# MotorController_ControlV1_1.net
KiCad netlist of a schematic drawn in Altium Designer
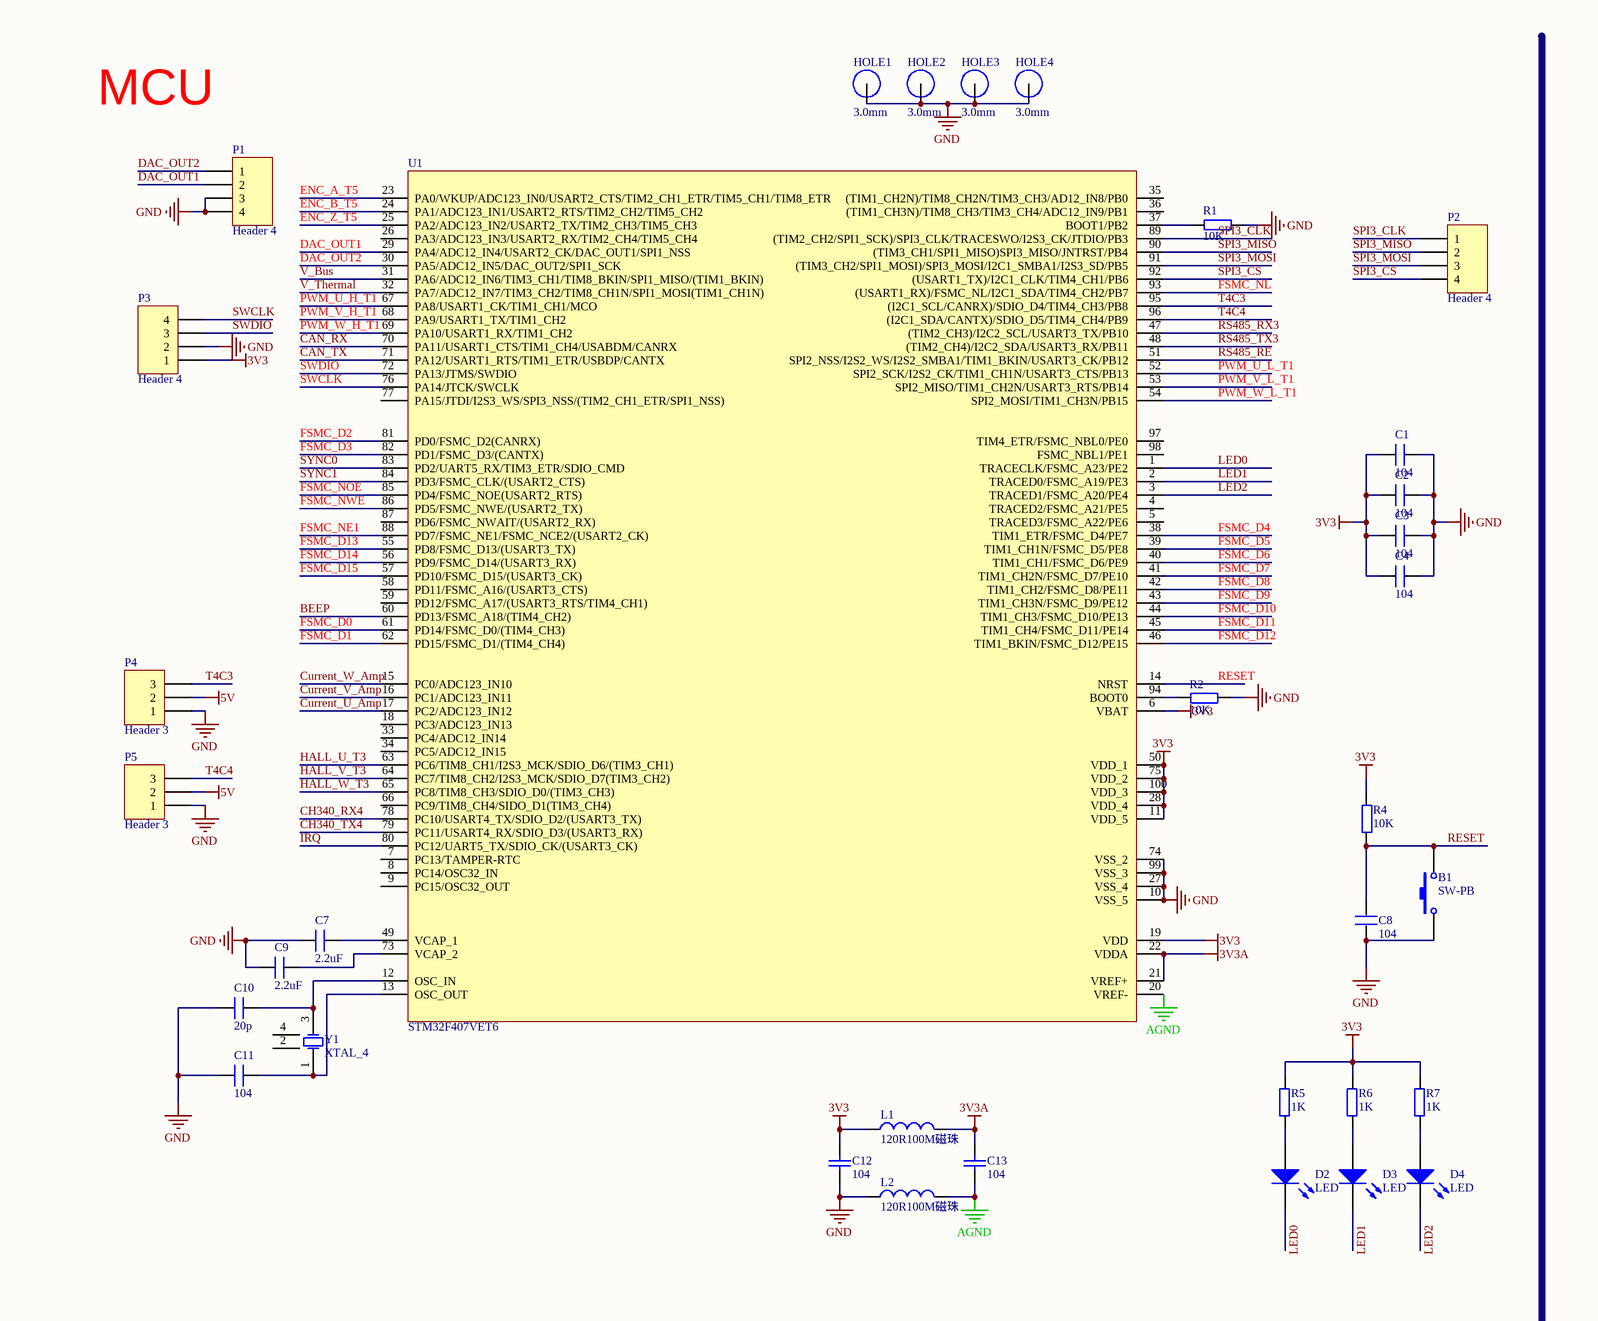
[diagram p0: MotorController_ControlV1.1.SchDoc, top left]
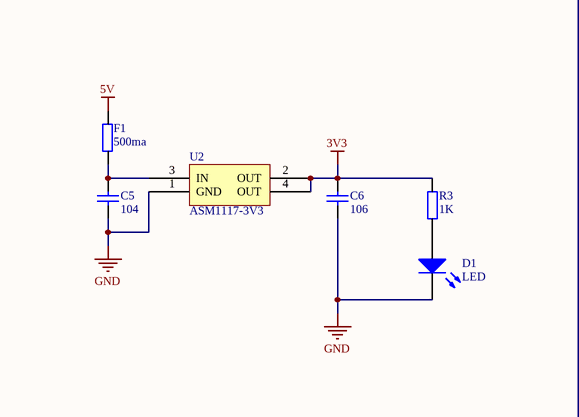
[diagram p1: MotorController_ControlV1.1.SchDoc, top middle]
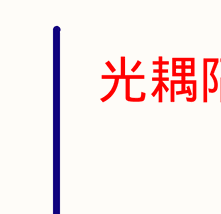
[diagram p2: MotorController_ControlV1.1.SchDoc, top right]
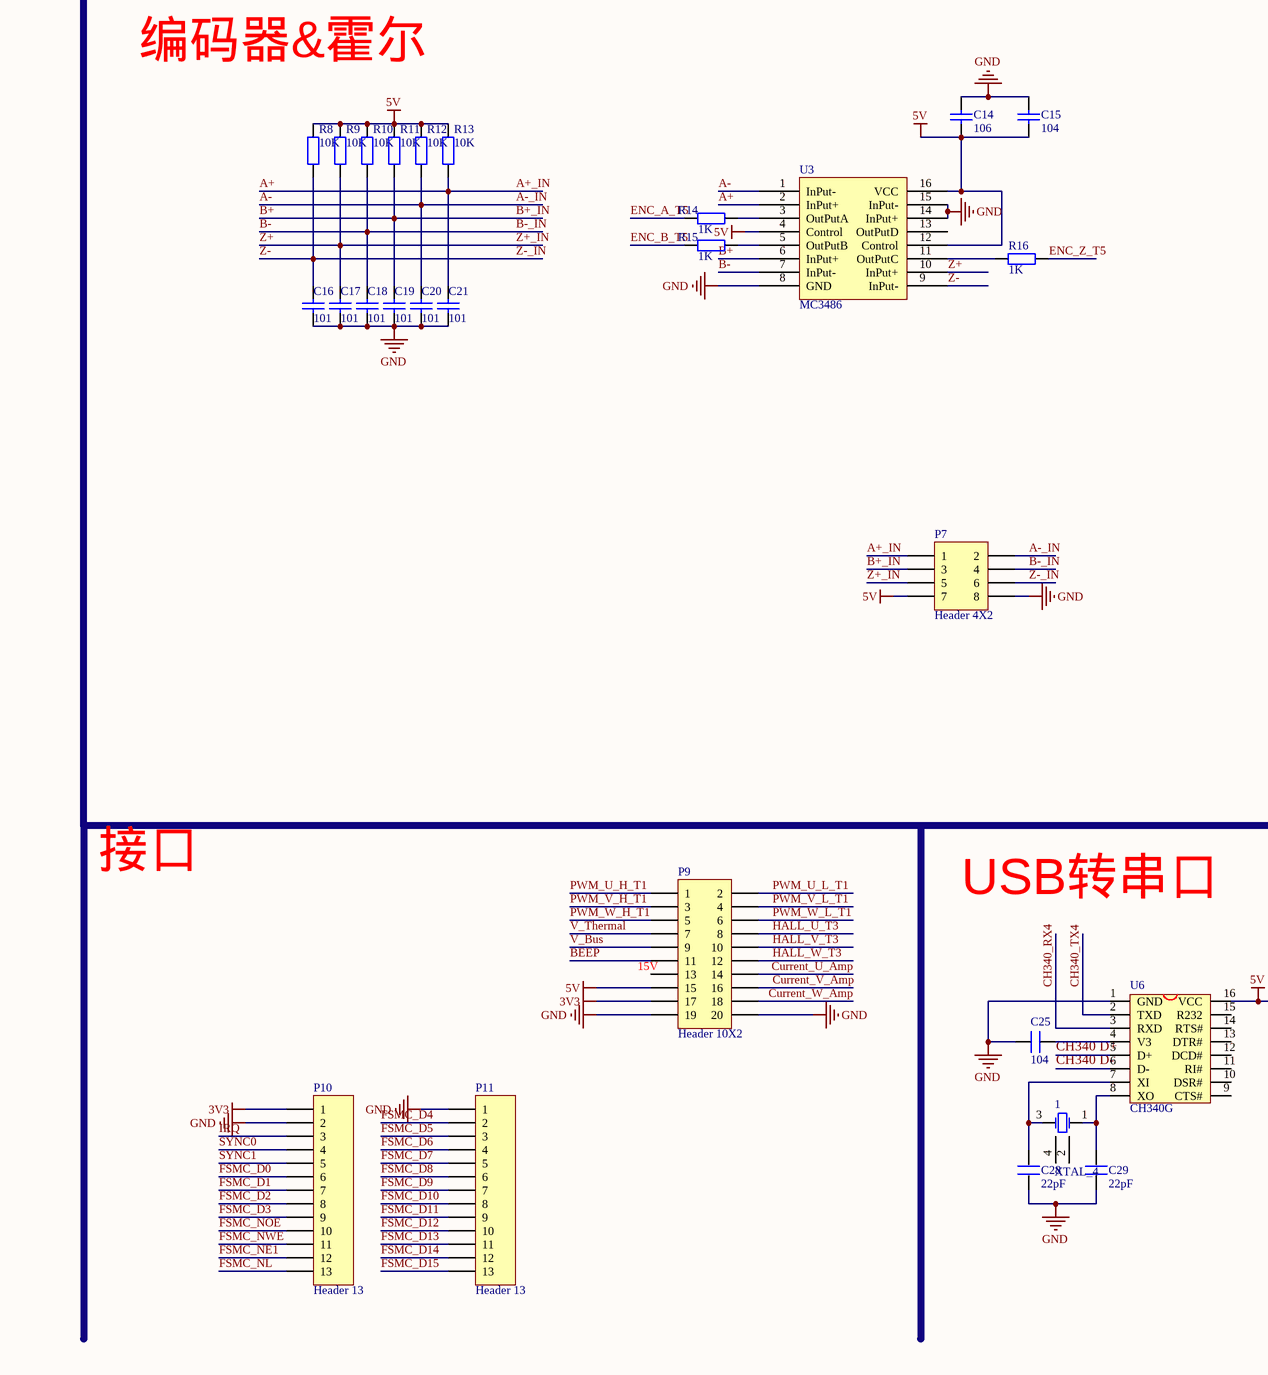
[diagram p3: MotorController_ControlV1.1.SchDoc, bottom middle]
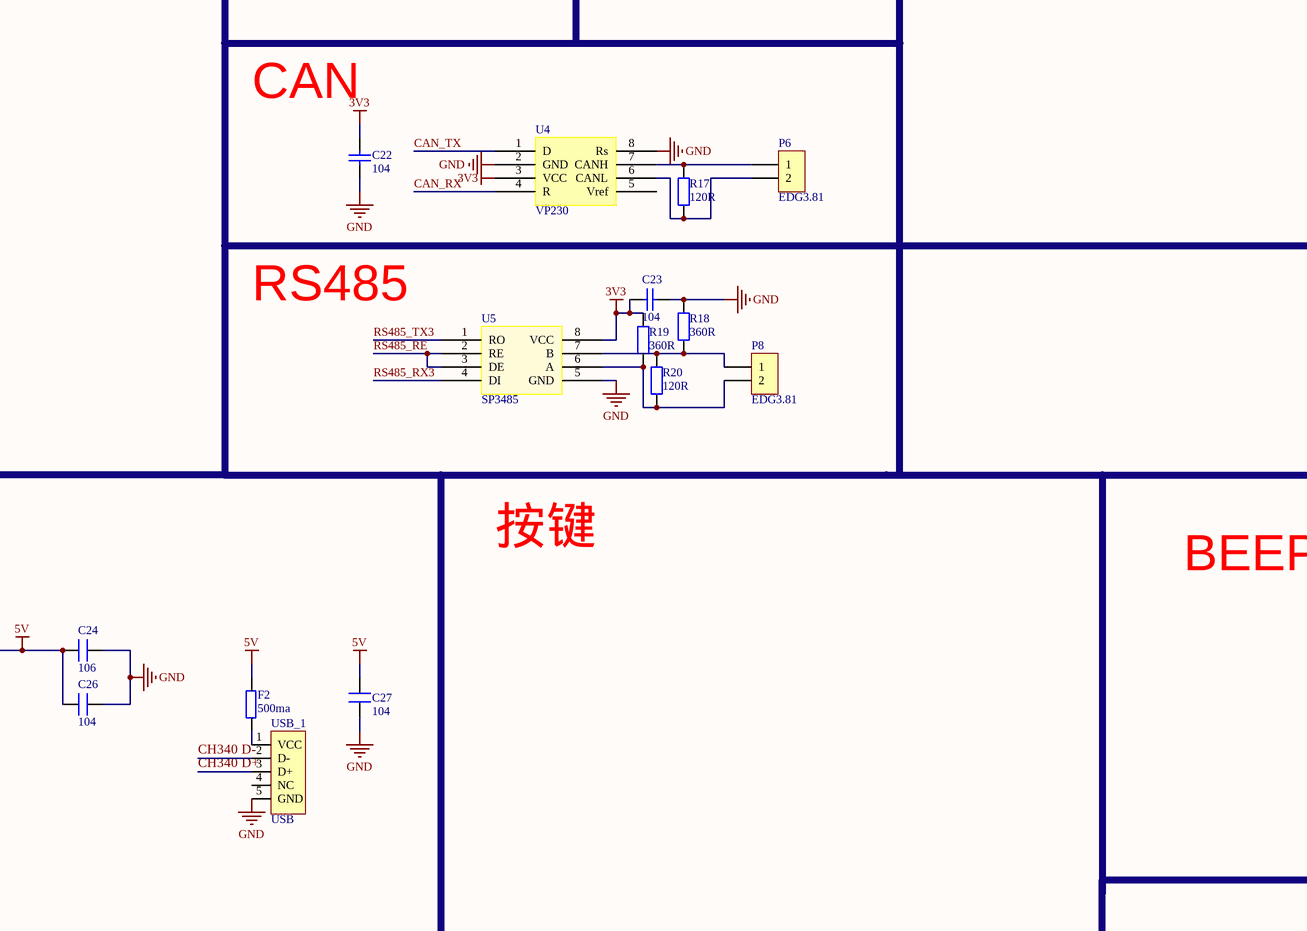
[diagram p4: MotorController_ControlV1.1.SchDoc, bottom right]

(export (version "E")
  (design (tool "Eeschema 10.0.6"))
  (components
    (comp (ref "1")
      (value "XTAL_4")
      (footprint "OSC 3225-4P")
      (description "Crystal Oscillator")
      (fields (field (name "PUBLISHER") "Altium Limited"))
      (libsource (lib "MYSchlib") (part "XTAL_4"))
    )
    (comp (ref "B1")
      (value "SW-PB")
      (footprint "TSW DIP-3*6*5_V")
      (description "Switch")
      (fields (field (name "PUBLISHER") "Altium Limited"))
      (libsource (lib "Miscellaneous Devices") (part "SW-PB"))
    )
    (comp (ref "C1") (value "104") (footprint "0603_C") (libsource (lib "MYSchlib") (part "C")))
    (comp (ref "C2") (value "104") (footprint "0603_C") (libsource (lib "MYSchlib") (part "C")))
    (comp (ref "C3") (value "104") (footprint "0603_C") (libsource (lib "MYSchlib") (part "C")))
    (comp (ref "C4") (value "104") (footprint "0603_C") (libsource (lib "MYSchlib") (part "C")))
    (comp (ref "C5")
      (value "104")
      (footprint "0603_C")
      (description "C")
      (fields (field (name "PUBLISHER") "Altium Limited"))
      (libsource (lib "RLC") (part "C"))
    )
    (comp (ref "C6")
      (value "106")
      (footprint "0603_C")
      (description "C")
      (fields (field (name "PUBLISHER") "Altium Limited"))
      (libsource (lib "RLC") (part "C"))
    )
    (comp (ref "C7") (value "2.2uF") (footprint "0603_C") (libsource (lib "MYSchlib") (part "C")))
    (comp (ref "C8") (value "104") (footprint "0603_C") (libsource (lib "MYSchlib") (part "C")))
    (comp (ref "C9") (value "2.2uF") (footprint "0603_C") (libsource (lib "MYSchlib") (part "C")))
    (comp (ref "C10") (value "20p") (footprint "0603_C") (libsource (lib "MYSchlib") (part "C")))
    (comp (ref "C11") (value "104") (footprint "0603_C") (libsource (lib "MYSchlib") (part "C")))
    (comp (ref "C12")
      (value "104")
      (footprint "0603_C")
      (description "C")
      (fields (field (name "PUBLISHER") "Altium Limited"))
      (libsource (lib "RLC") (part "C"))
    )
    (comp (ref "C13")
      (value "104")
      (footprint "0603_C")
      (description "C")
      (fields (field (name "PUBLISHER") "Altium Limited"))
      (libsource (lib "RLC") (part "C"))
    )
    (comp (ref "C14")
      (value "106")
      (footprint "0603_C")
      (description "Capacitor")
      (fields (field (name "Comment") "Cap") (field (name "PUBLISHER") "Altium Limited"))
      (libsource (lib "Miscellaneous Devices") (part "Cap"))
    )
    (comp (ref "C15")
      (value "104")
      (footprint "0603_C")
      (description "Capacitor")
      (fields (field (name "Comment") "Cap") (field (name "PUBLISHER") "Altium Limited"))
      (libsource (lib "Miscellaneous Devices") (part "Cap"))
    )
    (comp (ref "C16")
      (value "101")
      (footprint "0603_C")
      (description "Capacitor")
      (fields (field (name "Comment") "Cap") (field (name "PUBLISHER") "Altium Limited"))
      (libsource (lib "Miscellaneous Devices") (part "Cap"))
    )
    (comp (ref "C17")
      (value "101")
      (footprint "0603_C")
      (description "Capacitor")
      (fields (field (name "Comment") "Cap") (field (name "PUBLISHER") "Altium Limited"))
      (libsource (lib "Miscellaneous Devices") (part "Cap"))
    )
    (comp (ref "C18")
      (value "101")
      (footprint "0603_C")
      (description "Capacitor")
      (fields (field (name "Comment") "Cap") (field (name "PUBLISHER") "Altium Limited"))
      (libsource (lib "Miscellaneous Devices") (part "Cap"))
    )
    (comp (ref "C19")
      (value "101")
      (footprint "0603_C")
      (description "Capacitor")
      (fields (field (name "Comment") "Cap") (field (name "PUBLISHER") "Altium Limited"))
      (libsource (lib "Miscellaneous Devices") (part "Cap"))
    )
    (comp (ref "C20")
      (value "101")
      (footprint "0603_C")
      (description "Capacitor")
      (fields (field (name "Comment") "Cap") (field (name "PUBLISHER") "Altium Limited"))
      (libsource (lib "Miscellaneous Devices") (part "Cap"))
    )
    (comp (ref "C21")
      (value "101")
      (footprint "0603_C")
      (description "Capacitor")
      (fields (field (name "Comment") "Cap") (field (name "PUBLISHER") "Altium Limited"))
      (libsource (lib "Miscellaneous Devices") (part "Cap"))
    )
    (comp (ref "C22")
      (value "104")
      (footprint "0603_C")
      (description "Capacitor")
      (fields (field (name "Comment") "Cap") (field (name "PUBLISHER") "Altium Limited"))
      (libsource (lib "Miscellaneous Devices") (part "Cap"))
    )
    (comp (ref "C23")
      (value "104")
      (footprint "0603_C")
      (description "Capacitor")
      (fields (field (name "Comment") "Cap") (field (name "PUBLISHER") "Altium Limited"))
      (libsource (lib "Miscellaneous Devices") (part "Cap"))
    )
    (comp (ref "C24") (value "106") (footprint "0603_C") (libsource (lib "战舰STM32开发板底板封装库") (part "C")))
    (comp (ref "C25") (value "104") (footprint "0603_C") (libsource (lib "战舰STM32开发板底板封装库") (part "C")))
    (comp (ref "C26") (value "104") (footprint "0603_C") (libsource (lib "战舰STM32开发板底板封装库") (part "C")))
    (comp (ref "C27") (value "104") (footprint "0603_C") (libsource (lib "战舰STM32开发板底板封装库") (part "C")))
    (comp (ref "C28") (value "22pF") (footprint "0603_C") (libsource (lib "战舰STM32开发板底板封装库") (part "C")))
    (comp (ref "C29") (value "22pF") (footprint "0603_C") (libsource (lib "战舰STM32开发板底板封装库") (part "C")))
    (comp (ref "D1") (value "LED") (footprint "0603_LED") (libsource (lib "MYSchlib") (part "LED")))
    (comp (ref "D2") (value "LED") (footprint "0603_LED") (libsource (lib "MYSchlib") (part "LED")))
    (comp (ref "D3") (value "LED") (footprint "0603_LED") (libsource (lib "MYSchlib") (part "LED")))
    (comp (ref "D4") (value "LED") (footprint "0603_LED") (libsource (lib "MYSchlib") (part "LED")))
    (comp (ref "F1") (value "500ma") (footprint "FU 0805") (libsource (lib "MYSchlib") (part "R")))
    (comp (ref "F2") (value "500ma") (footprint "FU 0805") (libsource (lib "MYSchlib") (part "R")))
    (comp (ref "HOLE1")
      (value "3.0mm")
      (footprint "M2.5x6+6_L")
      (fields (field (name "Comment") "HOLE"))
      (libsource (lib "MYSchlib") (part "HOLE"))
    )
    (comp (ref "HOLE2")
      (value "3.0mm")
      (footprint "M2.5x6+6_L")
      (fields (field (name "Comment") "HOLE"))
      (libsource (lib "MYSchlib") (part "HOLE"))
    )
    (comp (ref "HOLE3")
      (value "3.0mm")
      (footprint "M2.5x6+6_L")
      (fields (field (name "Comment") "HOLE"))
      (libsource (lib "MYSchlib") (part "HOLE"))
    )
    (comp (ref "HOLE4")
      (value "3.0mm")
      (footprint "M2.5x6+6_L")
      (fields (field (name "Comment") "HOLE"))
      (libsource (lib "MYSchlib") (part "HOLE"))
    )
    (comp (ref "L1")
      (value "120R100M磁珠")
      (footprint "0603_R")
      (description "L")
      (fields (field (name "PUBLISHER") "Altium Limited"))
      (libsource (lib "MYSchlib") (part "L_1"))
    )
    (comp (ref "L2")
      (value "120R100M磁珠")
      (footprint "0603_R")
      (description "L")
      (fields (field (name "PUBLISHER") "Altium Limited"))
      (libsource (lib "MYSchlib") (part "L_1"))
    )
    (comp (ref "P1")
      (value "Header 4")
      (footprint "HDR2.54-LI-4P")
      (description "Header, 4-Pin")
      (fields (field (name "PUBLISHER") "Altium Limited"))
      (libsource (lib "Miscellaneous Connectors") (part "Header 4"))
    )
    (comp (ref "P2")
      (value "Header 4")
      (footprint "HDR1X4")
      (description "Header, 4-Pin")
      (fields (field (name "PUBLISHER") "Altium Limited"))
      (libsource (lib "Miscellaneous Connectors") (part "Header 4"))
    )
    (comp (ref "P3")
      (value "Header 4")
      (footprint "HDR1X4")
      (description "Header, 4-Pin")
      (fields (field (name "PUBLISHER") "Altium Limited"))
      (libsource (lib "MYSchlib") (part "Header 4"))
    )
    (comp (ref "P4")
      (value "Header 3")
      (footprint "HDR1X3")
      (description "Header, 3-Pin")
      (fields (field (name "PUBLISHER") "Altium Limited"))
      (libsource (lib "Miscellaneous Connectors") (part "Header 3"))
    )
    (comp (ref "P5")
      (value "Header 3")
      (footprint "HDR1X3")
      (description "Header, 3-Pin")
      (fields (field (name "PUBLISHER") "Altium Limited"))
      (libsource (lib "Miscellaneous Connectors") (part "Header 3"))
    )
    (comp (ref "P6")
      (value "EDG3.81")
      (footprint "3.81EDG_2*1W")
      (fields (field (name "PUBLISHER") "Altium Limited"))
      (libsource (lib "MYSchlib") (part "HT3.96"))
    )
    (comp (ref "P7")
      (value "Header 4X2")
      (footprint "MYPcbLib:HDR2.54-WI-2x4P")
      (description "Header, 4-Pin, Dual row")
      (fields (field (name "PUBLISHER") "Altium Limited"))
      (libsource (lib "Miscellaneous Connectors") (part "Header 4X2"))
    )
    (comp (ref "P8")
      (value "EDG3.81")
      (footprint "3.81EDG_2*1W")
      (fields (field (name "PUBLISHER") "Altium Limited"))
      (libsource (lib "MYSchlib") (part "HT3.96"))
    )
    (comp (ref "P9")
      (value "Header 10X2")
      (footprint "MYPcbLib:HDR2.54-LI-2x10P")
      (description "Header, 10-Pin, Dual row")
      (fields (field (name "PUBLISHER") "Altium Limited"))
      (libsource (lib "Miscellaneous Connectors") (part "Header 10X2"))
    )
    (comp (ref "P10")
      (value "Header 13")
      (footprint "HDR2.54-LI-13P")
      (description "Header, 13-Pin")
      (fields (field (name "PUBLISHER") "Altium Limited"))
      (libsource (lib "Miscellaneous Connectors") (part "Header 13"))
    )
    (comp (ref "P11")
      (value "Header 13")
      (footprint "HDR2.54-LI-13P")
      (description "Header, 13-Pin")
      (fields (field (name "PUBLISHER") "Altium Limited"))
      (libsource (lib "Miscellaneous Connectors") (part "Header 13"))
    )
    (comp (ref "R1") (value "10K") (footprint "0603_R") (libsource (lib "MYSchlib") (part "R")))
    (comp (ref "R2") (value "10K") (footprint "0603_R") (libsource (lib "MYSchlib") (part "R")))
    (comp (ref "R3") (value "1K") (footprint "0603_R") (libsource (lib "MYSchlib") (part "R")))
    (comp (ref "R4") (value "10K") (footprint "0603_R") (libsource (lib "MYSchlib") (part "R")))
    (comp (ref "R5") (value "1K") (footprint "0603_R") (libsource (lib "MYSchlib") (part "R")))
    (comp (ref "R6") (value "1K") (footprint "0603_R") (libsource (lib "MYSchlib") (part "R")))
    (comp (ref "R7") (value "1K") (footprint "0603_R") (libsource (lib "MYSchlib") (part "R")))
    (comp (ref "R8")
      (value "10K")
      (footprint "0603_R")
      (description "Resistor")
      (fields (field (name "Comment") "Res2") (field (name "PUBLISHER") "Altium Limited"))
      (libsource (lib "Miscellaneous Devices") (part "Res2"))
    )
    (comp (ref "R9")
      (value "10K")
      (footprint "0603_R")
      (description "Resistor")
      (fields (field (name "Comment") "Res2") (field (name "PUBLISHER") "Altium Limited"))
      (libsource (lib "Miscellaneous Devices") (part "Res2"))
    )
    (comp (ref "R10")
      (value "10K")
      (footprint "0603_R")
      (description "Resistor")
      (fields (field (name "Comment") "Res2") (field (name "PUBLISHER") "Altium Limited"))
      (libsource (lib "Miscellaneous Devices") (part "Res2"))
    )
    (comp (ref "R11")
      (value "10K")
      (footprint "0603_R")
      (description "Resistor")
      (fields (field (name "Comment") "Res2") (field (name "PUBLISHER") "Altium Limited"))
      (libsource (lib "Miscellaneous Devices") (part "Res2"))
    )
    (comp (ref "R12")
      (value "10K")
      (footprint "0603_R")
      (description "Resistor")
      (fields (field (name "Comment") "Res2") (field (name "PUBLISHER") "Altium Limited"))
      (libsource (lib "Miscellaneous Devices") (part "Res2"))
    )
    (comp (ref "R13")
      (value "10K")
      (footprint "0603_R")
      (description "Resistor")
      (fields (field (name "Comment") "Res2") (field (name "PUBLISHER") "Altium Limited"))
      (libsource (lib "Miscellaneous Devices") (part "Res2"))
    )
    (comp (ref "R14")
      (value "1K")
      (footprint "0603_R")
      (description "Resistor")
      (fields (field (name "Comment") "Res2") (field (name "PUBLISHER") "Altium Limited"))
      (libsource (lib "") (part "Res2_1"))
    )
    (comp (ref "R15")
      (value "1K")
      (footprint "0603_R")
      (description "Resistor")
      (fields (field (name "Comment") "Res2") (field (name "PUBLISHER") "Altium Limited"))
      (libsource (lib "") (part "Res2_1"))
    )
    (comp (ref "R16")
      (value "1K")
      (footprint "0603_R")
      (description "Resistor")
      (fields (field (name "Comment") "Res2") (field (name "PUBLISHER") "Altium Limited"))
      (libsource (lib "") (part "Res2_2"))
    )
    (comp (ref "R17")
      (value "120R")
      (footprint "0603_R")
      (description "Resistor")
      (fields (field (name "Comment") "Res2") (field (name "PUBLISHER") "Altium Limited"))
      (libsource (lib "MySchLib") (part "Res2"))
    )
    (comp (ref "R18")
      (value "360R")
      (footprint "0603_R")
      (description "Resistor")
      (fields (field (name "Comment") "Res2") (field (name "PUBLISHER") "Altium Limited"))
      (libsource (lib "MySchLib") (part "Res2"))
    )
    (comp (ref "R19")
      (value "360R")
      (footprint "0603_R")
      (description "Resistor")
      (fields (field (name "Comment") "Res2") (field (name "PUBLISHER") "Altium Limited"))
      (libsource (lib "MySchLib") (part "Res2"))
    )
    (comp (ref "R20")
      (value "120R")
      (footprint "0603_R")
      (description "Resistor")
      (fields (field (name "Comment") "Res2") (field (name "PUBLISHER") "Altium Limited"))
      (libsource (lib "MySchLib") (part "Res2"))
    )
    (comp (ref "U1")
      (value "STM32F407VET6")
      (footprint "LQFP-100_M")
      (libsource (lib "MYSchlib") (part "STM32F407VET6"))
    )
    (comp (ref "U2")
      (value "ASM1117-3V3")
      (footprint "SOT-223")
      (description "3.3V稳压芯片")
      (libsource (lib "MYSchlib") (part "ASM1117"))
    )
    (comp (ref "U3") (value "MC3486") (footprint "SO-16N") (libsource (lib "AM26LS32") (part "Component_1")))
    (comp (ref "U4") (value "VP230") (footprint "SOP-8") (libsource (lib "MYSchlib") (part "VP230")))
    (comp (ref "U5") (value "SP3485") (footprint "SOP-8") (libsource (lib "MYSchlib") (part "SP3485")))
    (comp (ref "U6")
      (value "CH340G")
      (footprint "SOP16")
      (description "USB2UART")
      (libsource (lib "MYSchlib") (part "CH340G"))
    )
    (comp (ref "USB_1") (value "USB") (footprint "USB_AB") (libsource (lib "战舰STM32开发板底板封装库") (part "USB5")))
    (comp (ref "Y1")
      (value "XTAL_4")
      (footprint "OSC 5032-4P")
      (description "Crystal Oscillator")
      (fields (field (name "PUBLISHER") "Altium Limited"))
      (libsource (lib "MYSchlib") (part "XTAL_4"))
    )
  )
  (nets
    (net (code "1") (name "/A+") (class "Default")
      (node (ref "C21") (pin "1") (pinfunction "1_1") (pintype "passive"))
      (node (ref "P7") (pin "1") (pinfunction "1_1") (pintype "passive"))
      (node (ref "R13") (pin "2") (pinfunction "2_2") (pintype "passive"))
      (node (ref "U3") (pin "2") (pinfunction "InPut+_2") (pintype "passive"))
    )
    (net (code "2") (name "/A-") (class "Default")
      (node (ref "C20") (pin "1") (pinfunction "1_1") (pintype "passive"))
      (node (ref "P7") (pin "2") (pinfunction "2_2") (pintype "passive"))
      (node (ref "R12") (pin "2") (pinfunction "2_2") (pintype "passive"))
      (node (ref "U3") (pin "1") (pinfunction "InPut-_1") (pintype "passive"))
    )
    (net (code "3") (name "/B+") (class "Default")
      (node (ref "C19") (pin "1") (pinfunction "1_1") (pintype "passive"))
      (node (ref "P7") (pin "3") (pinfunction "3_3") (pintype "passive"))
      (node (ref "R11") (pin "2") (pinfunction "2_2") (pintype "passive"))
      (node (ref "U3") (pin "6") (pinfunction "InPut+_6") (pintype "passive"))
    )
    (net (code "4") (name "/B-") (class "Default")
      (node (ref "C18") (pin "1") (pinfunction "1_1") (pintype "passive"))
      (node (ref "P7") (pin "4") (pinfunction "4_4") (pintype "passive"))
      (node (ref "R10") (pin "2") (pinfunction "2_2") (pintype "passive"))
      (node (ref "U3") (pin "7") (pinfunction "InPut-_7") (pintype "passive"))
    )
    (net (code "5") (name "/BEEP") (class "Default")
      (node (ref "P9") (pin "11") (pinfunction "11_11") (pintype "passive"))
      (node (ref "U1") (pin "60") (pinfunction "PD13/FSMC_A18/(TIM4_CH2)_60") (pintype "passive"))
    )
    (net (code "6") (name "/CAN_RX") (class "Default")
      (node (ref "U1") (pin "70") (pinfunction "PA11/USART1_CTS/TIM1_CH4/USABDM/CANRX_70") (pintype "passive"))
      (node (ref "U4") (pin "4") (pinfunction "R_4") (pintype "passive"))
    )
    (net (code "7") (name "/CAN_TX") (class "Default")
      (node (ref "U1") (pin "71") (pinfunction "PA12/USART1_RTS/TIM1_ETR/USBDP/CANTX_71") (pintype "passive"))
      (node (ref "U4") (pin "1") (pinfunction "D_1") (pintype "passive"))
    )
    (net (code "8") (name "/CH340 D+") (class "Default")
      (node (ref "U6") (pin "5") (pinfunction "D+_5") (pintype "passive"))
      (node (ref "USB_1") (pin "3") (pinfunction "D+_3") (pintype "passive"))
    )
    (net (code "9") (name "/CH340 D-") (class "Default")
      (node (ref "U6") (pin "6") (pinfunction "D-_6") (pintype "passive"))
      (node (ref "USB_1") (pin "2") (pinfunction "D-_2") (pintype "passive"))
    )
    (net (code "10") (name "/CH340_RX4") (class "Default")
      (node (ref "U1") (pin "78") (pinfunction "PC10/USART4_TX/SDIO_D2/(USART3_TX)_78") (pintype "passive"))
      (node (ref "U6") (pin "3") (pinfunction "RXD_3") (pintype "passive"))
    )
    (net (code "11") (name "/CH340_TX4") (class "Default")
      (node (ref "U1") (pin "79") (pinfunction "PC11/USART4_RX/SDIO_D3/(USART3_RX)_79") (pintype "passive"))
      (node (ref "U6") (pin "2") (pinfunction "TXD_2") (pintype "passive"))
    )
    (net (code "12") (name "/Current_U_Amp") (class "Default")
      (node (ref "P9") (pin "14") (pinfunction "14_14") (pintype "passive"))
      (node (ref "U1") (pin "17") (pinfunction "PC2/ADC123_IN12_17") (pintype "passive"))
    )
    (net (code "13") (name "/Current_V_Amp") (class "Default")
      (node (ref "P9") (pin "16") (pinfunction "16_16") (pintype "passive"))
      (node (ref "U1") (pin "16") (pinfunction "PC1/ADC123_IN11_16") (pintype "passive"))
    )
    (net (code "14") (name "/Current_W_Amp") (class "Default")
      (node (ref "P9") (pin "18") (pinfunction "18_18") (pintype "passive"))
      (node (ref "U1") (pin "15") (pinfunction "PC0/ADC123_IN10_15") (pintype "passive"))
    )
    (net (code "15") (name "/DAC_OUT1") (class "Default")
      (node (ref "P1") (pin "2") (pinfunction "2_2") (pintype "passive"))
      (node (ref "U1") (pin "29") (pinfunction "PA4/ADC12_IN4/USART2_CK/DAC_OUT1/SPI1_NSS_29") (pintype "passive"))
    )
    (net (code "16") (name "/DAC_OUT2") (class "Default")
      (node (ref "P1") (pin "1") (pinfunction "1_1") (pintype "passive"))
      (node (ref "U1") (pin "30") (pinfunction "PA5/ADC12_IN5/DAC_OUT2/SPI1_SCK_30") (pintype "passive"))
    )
    (net (code "17") (name "/ENC_A_T5") (class "Default")
      (node (ref "R14") (pin "2") (pinfunction "2_2") (pintype "passive"))
      (node (ref "U1") (pin "23") (pinfunction "PA0/WKUP/ADC123_IN0/USART2_CTS/TIM2_CH1_ETR/TIM5_CH1/TIM8_ETR_23") (pintype "passive"))
    )
    (net (code "18") (name "/ENC_B_T5") (class "Default")
      (node (ref "R15") (pin "2") (pinfunction "2_2") (pintype "passive"))
      (node (ref "U1") (pin "24") (pinfunction "PA1/ADC123_IN1/USART2_RTS/TIM2_CH2/TIM5_CH2_24") (pintype "passive"))
    )
    (net (code "19") (name "/ENC_Z_T5") (class "Default")
      (node (ref "R16") (pin "2") (pinfunction "2_2") (pintype "passive"))
      (node (ref "U1") (pin "25") (pinfunction "PA2/ADC123_IN2/USART2_TX/TIM2_CH3/TIM5_CH3_25") (pintype "passive"))
    )
    (net (code "20") (name "/FSMC_D0") (class "Default")
      (node (ref "P10") (pin "6") (pinfunction "6_6") (pintype "passive"))
      (node (ref "U1") (pin "61") (pinfunction "PD14/FSMC_D0/(TIM4_CH3)_61") (pintype "passive"))
    )
    (net (code "21") (name "/FSMC_D1") (class "Default")
      (node (ref "P10") (pin "7") (pinfunction "7_7") (pintype "passive"))
      (node (ref "U1") (pin "62") (pinfunction "PD15/FSMC_D1/(TIM4_CH4)_62") (pintype "passive"))
    )
    (net (code "22") (name "/FSMC_D2") (class "Default")
      (node (ref "P10") (pin "8") (pinfunction "8_8") (pintype "passive"))
      (node (ref "U1") (pin "81") (pinfunction "PD0/FSMC_D2(CANRX)_81") (pintype "passive"))
    )
    (net (code "23") (name "/FSMC_D3") (class "Default")
      (node (ref "P10") (pin "9") (pinfunction "9_9") (pintype "passive"))
      (node (ref "U1") (pin "82") (pinfunction "PD1/FSMC_D3/(CANTX)_82") (pintype "passive"))
    )
    (net (code "24") (name "/FSMC_D4") (class "Default")
      (node (ref "P11") (pin "2") (pinfunction "2_2") (pintype "passive"))
      (node (ref "U1") (pin "38") (pinfunction "TIM1_ETR/FSMC_D4/PE7_38") (pintype "passive"))
    )
    (net (code "25") (name "/FSMC_D5") (class "Default")
      (node (ref "P11") (pin "3") (pinfunction "3_3") (pintype "passive"))
      (node (ref "U1") (pin "39") (pinfunction "TIM1_CH1N/FSMC_D5/PE8_39") (pintype "passive"))
    )
    (net (code "26") (name "/FSMC_D6") (class "Default")
      (node (ref "P11") (pin "4") (pinfunction "4_4") (pintype "passive"))
      (node (ref "U1") (pin "40") (pinfunction "TIM1_CH1/FSMC_D6/PE9_40") (pintype "passive"))
    )
    (net (code "27") (name "/FSMC_D7") (class "Default")
      (node (ref "P11") (pin "5") (pinfunction "5_5") (pintype "passive"))
      (node (ref "U1") (pin "41") (pinfunction "TIM1_CH2N/FSMC_D7/PE10_41") (pintype "passive"))
    )
    (net (code "28") (name "/FSMC_D8") (class "Default")
      (node (ref "P11") (pin "6") (pinfunction "6_6") (pintype "passive"))
      (node (ref "U1") (pin "42") (pinfunction "TIM1_CH2/FSMC_D8/PE11_42") (pintype "passive"))
    )
    (net (code "29") (name "/FSMC_D9") (class "Default")
      (node (ref "P11") (pin "7") (pinfunction "7_7") (pintype "passive"))
      (node (ref "U1") (pin "43") (pinfunction "TIM1_CH3N/FSMC_D9/PE12_43") (pintype "passive"))
    )
    (net (code "30") (name "/FSMC_D10") (class "Default")
      (node (ref "P11") (pin "8") (pinfunction "8_8") (pintype "passive"))
      (node (ref "U1") (pin "44") (pinfunction "TIM1_CH3/FSMC_D10/PE13_44") (pintype "passive"))
    )
    (net (code "31") (name "/FSMC_D11") (class "Default")
      (node (ref "P11") (pin "9") (pinfunction "9_9") (pintype "passive"))
      (node (ref "U1") (pin "45") (pinfunction "TIM1_CH4/FSMC_D11/PE14_45") (pintype "passive"))
    )
    (net (code "32") (name "/FSMC_D12") (class "Default")
      (node (ref "P11") (pin "10") (pinfunction "10_10") (pintype "passive"))
      (node (ref "U1") (pin "46") (pinfunction "TIM1_BKIN/FSMC_D12/PE15_46") (pintype "passive"))
    )
    (net (code "33") (name "/FSMC_D13") (class "Default")
      (node (ref "P11") (pin "11") (pinfunction "11_11") (pintype "passive"))
      (node (ref "U1") (pin "55") (pinfunction "PD8/FSMC_D13/(USART3_TX)_55") (pintype "passive"))
    )
    (net (code "34") (name "/FSMC_D14") (class "Default")
      (node (ref "P11") (pin "12") (pinfunction "12_12") (pintype "passive"))
      (node (ref "U1") (pin "56") (pinfunction "PD9/FSMC_D14/(USART3_RX)_56") (pintype "passive"))
    )
    (net (code "35") (name "/FSMC_D15") (class "Default")
      (node (ref "P11") (pin "13") (pinfunction "13_13") (pintype "passive"))
      (node (ref "U1") (pin "57") (pinfunction "PD10/FSMC_D15/(USART3_CK)_57") (pintype "passive"))
    )
    (net (code "36") (name "/FSMC_NE1") (class "Default")
      (node (ref "P10") (pin "12") (pinfunction "12_12") (pintype "passive"))
      (node (ref "U1") (pin "88") (pinfunction "PD7/FSMC_NE1/FSMC_NCE2/(USART2_CK)_88") (pintype "passive"))
    )
    (net (code "37") (name "/FSMC_NL") (class "Default")
      (node (ref "P10") (pin "13") (pinfunction "13_13") (pintype "passive"))
      (node (ref "U1") (pin "93") (pinfunction "(USART1_RX)/FSMC_NL/I2C1_SDA/TIM4_CH2/PB7_93") (pintype "passive"))
    )
    (net (code "38") (name "/FSMC_NOE") (class "Default")
      (node (ref "P10") (pin "10") (pinfunction "10_10") (pintype "passive"))
      (node (ref "U1") (pin "85") (pinfunction "PD4/FSMC_NOE(USART2_RTS)_85") (pintype "passive"))
    )
    (net (code "39") (name "/FSMC_NWE") (class "Default")
      (node (ref "P10") (pin "11") (pinfunction "11_11") (pintype "passive"))
      (node (ref "U1") (pin "86") (pinfunction "PD5/FSMC_NWE/(USART2_TX)_86") (pintype "passive"))
    )
    (net (code "40") (name "/HALL_U_T3") (class "Default")
      (node (ref "P9") (pin "8") (pinfunction "8_8") (pintype "passive"))
      (node (ref "U1") (pin "63") (pinfunction "PC6/TIM8_CH1/I2S3_MCK/SDIO_D6/(TIM3_CH1)_63") (pintype "passive"))
    )
    (net (code "41") (name "/HALL_V_T3") (class "Default")
      (node (ref "P9") (pin "10") (pinfunction "10_10") (pintype "passive"))
      (node (ref "U1") (pin "64") (pinfunction "PC7/TIM8_CH2/I2S3_MCK/SDIO_D7(TIM3_CH2)_64") (pintype "passive"))
    )
    (net (code "42") (name "/HALL_W_T3") (class "Default")
      (node (ref "P9") (pin "12") (pinfunction "12_12") (pintype "passive"))
      (node (ref "U1") (pin "65") (pinfunction "PC8/TIM8_CH3/SDIO_D0/(TIM3_CH3)_65") (pintype "passive"))
    )
    (net (code "43") (name "/IRQ") (class "Default")
      (node (ref "P10") (pin "3") (pinfunction "3_3") (pintype "passive"))
      (node (ref "U1") (pin "80") (pinfunction "PC12/UART5_TX/SDIO_CK/(USART3_CK)_80") (pintype "passive"))
    )
    (net (code "44") (name "/LED0") (class "Default")
      (node (ref "D2") (pin "2") (pinfunction "K_2") (pintype "passive"))
      (node (ref "U1") (pin "1") (pinfunction "TRACECLK/FSMC_A23/PE2_1") (pintype "passive"))
    )
    (net (code "45") (name "/LED1") (class "Default")
      (node (ref "D3") (pin "2") (pinfunction "K_2") (pintype "passive"))
      (node (ref "U1") (pin "2") (pinfunction "TRACED0/FSMC_A19/PE3_2") (pintype "passive"))
    )
    (net (code "46") (name "/LED2") (class "Default")
      (node (ref "D4") (pin "2") (pinfunction "K_2") (pintype "passive"))
      (node (ref "U1") (pin "3") (pinfunction "TRACED1/FSMC_A20/PE4_3") (pintype "passive"))
    )
    (net (code "47") (name "/PWM_U_H_T1") (class "Default")
      (node (ref "P9") (pin "1") (pinfunction "1_1") (pintype "passive"))
      (node (ref "U1") (pin "67") (pinfunction "PA8/USART1_CK/TIM1_CH1/MCO_67") (pintype "passive"))
    )
    (net (code "48") (name "/PWM_U_L_T1") (class "Default")
      (node (ref "P9") (pin "2") (pinfunction "2_2") (pintype "passive"))
      (node (ref "U1") (pin "52") (pinfunction "SPI2_SCK/I2S2_CK/TIM1_CH1N/USART3_CTS/PB13_52") (pintype "passive"))
    )
    (net (code "49") (name "/PWM_V_H_T1") (class "Default")
      (node (ref "P9") (pin "3") (pinfunction "3_3") (pintype "passive"))
      (node (ref "U1") (pin "68") (pinfunction "PA9/USART1_TX/TIM1_CH2_68") (pintype "passive"))
    )
    (net (code "50") (name "/PWM_V_L_T1") (class "Default")
      (node (ref "P9") (pin "4") (pinfunction "4_4") (pintype "passive"))
      (node (ref "U1") (pin "53") (pinfunction "SPI2_MISO/TIM1_CH2N/USART3_RTS/PB14_53") (pintype "passive"))
    )
    (net (code "51") (name "/PWM_W_H_T1") (class "Default")
      (node (ref "P9") (pin "5") (pinfunction "5_5") (pintype "passive"))
      (node (ref "U1") (pin "69") (pinfunction "PA10/USART1_RX/TIM1_CH2_69") (pintype "passive"))
    )
    (net (code "52") (name "/PWM_W_L_T1") (class "Default")
      (node (ref "P9") (pin "6") (pinfunction "6_6") (pintype "passive"))
      (node (ref "U1") (pin "54") (pinfunction "SPI2_MOSI/TIM1_CH3N/PB15_54") (pintype "passive"))
    )
    (net (code "53") (name "/RESET") (class "Default")
      (node (ref "B1") (pin "2") (pinfunction "2_2") (pintype "passive"))
      (node (ref "C8") (pin "2") (pintype "passive"))
      (node (ref "R4") (pin "1") (pintype "passive"))
      (node (ref "U1") (pin "14") (pinfunction "NRST_14") (pintype "passive"))
    )
    (net (code "54") (name "/RS485_RE") (class "Default")
      (node (ref "U1") (pin "51") (pinfunction "SPI2_NSS/I2S2_WS/I2S2_SMBA1/TIM1_BKIN/USART3_CK/PB12_51") (pintype "passive"))
      (node (ref "U5") (pin "2") (pinfunction "RE_2") (pintype "passive"))
      (node (ref "U5") (pin "3") (pinfunction "DE_3") (pintype "passive"))
    )
    (net (code "55") (name "/RS485_RX3") (class "Default")
      (node (ref "U1") (pin "47") (pinfunction "(TIM2_CH3)/I2C2_SCL/USART3_TX/PB10_47") (pintype "passive"))
      (node (ref "U5") (pin "4") (pinfunction "DI_4") (pintype "passive"))
    )
    (net (code "56") (name "/RS485_TX3") (class "Default")
      (node (ref "U1") (pin "48") (pinfunction "(TIM2_CH4)/I2C2_SDA/USART3_RX/PB11_48") (pintype "passive"))
      (node (ref "U5") (pin "1") (pinfunction "RO_1") (pintype "passive"))
    )
    (net (code "57") (name "/SPI3_CLK") (class "Default")
      (node (ref "P2") (pin "1") (pinfunction "1_1") (pintype "passive"))
      (node (ref "U1") (pin "89") (pinfunction "(TIM2_CH2/SPI1_SCK)/SPI3_CLK/TRACESWO/I2S3_CK/JTDIO/PB3_89") (pintype "passive"))
    )
    (net (code "58") (name "/SPI3_CS") (class "Default")
      (node (ref "P2") (pin "4") (pinfunction "4_4") (pintype "passive"))
      (node (ref "U1") (pin "92") (pinfunction "(USART1_TX)/I2C1_CLK/TIM4_CH1/PB6_92") (pintype "passive"))
    )
    (net (code "59") (name "/SPI3_MISO") (class "Default")
      (node (ref "P2") (pin "2") (pinfunction "2_2") (pintype "passive"))
      (node (ref "U1") (pin "90") (pinfunction "(TIM3_CH1/SPI1_MISO)SPI3_MISO/JNTRST/PB4_90") (pintype "passive"))
    )
    (net (code "60") (name "/SPI3_MOSI") (class "Default")
      (node (ref "P2") (pin "3") (pinfunction "3_3") (pintype "passive"))
      (node (ref "U1") (pin "91") (pinfunction "(TIM3_CH2/SPI1_MOSI)/SPI3_MOSI/I2C1_SMBA1/I2S3_SD/PB5_91") (pintype "passive"))
    )
    (net (code "61") (name "/SWCLK") (class "Default")
      (node (ref "P3") (pin "4") (pinfunction "4_4") (pintype "passive"))
      (node (ref "U1") (pin "76") (pinfunction "PA14/JTCK/SWCLK_76") (pintype "passive"))
    )
    (net (code "62") (name "/SWDIO") (class "Default")
      (node (ref "P3") (pin "3") (pinfunction "3_3") (pintype "passive"))
      (node (ref "U1") (pin "72") (pinfunction "PA13/JTMS/SWDIO_72") (pintype "passive"))
    )
    (net (code "63") (name "/SYNC0") (class "Default")
      (node (ref "P10") (pin "4") (pinfunction "4_4") (pintype "passive"))
      (node (ref "U1") (pin "83") (pinfunction "PD2/UART5_RX/TIM3_ETR/SDIO_CMD_83") (pintype "passive"))
    )
    (net (code "64") (name "/SYNC1") (class "Default")
      (node (ref "P10") (pin "5") (pinfunction "5_5") (pintype "passive"))
      (node (ref "U1") (pin "84") (pinfunction "PD3/FSMC_CLK/(USART2_CTS)_84") (pintype "passive"))
    )
    (net (code "65") (name "/T4C3") (class "Default")
      (node (ref "P4") (pin "3") (pinfunction "3_3") (pintype "passive"))
      (node (ref "U1") (pin "95") (pinfunction "(I2C1_SCL/CANRX)/SDIO_D4/TIM4_CH3/PB8_95") (pintype "passive"))
    )
    (net (code "66") (name "/T4C4") (class "Default")
      (node (ref "P5") (pin "3") (pinfunction "3_3") (pintype "passive"))
      (node (ref "U1") (pin "96") (pinfunction "(I2C1_SDA/CANTX)/SDIO_D5/TIM4_CH4/PB9_96") (pintype "passive"))
    )
    (net (code "67") (name "/V_Bus") (class "Default")
      (node (ref "P9") (pin "9") (pinfunction "9_9") (pintype "passive"))
      (node (ref "U1") (pin "31") (pinfunction "PA6/ADC12_IN6/TIM3_CH1/TIM8_BKIN/SPI1_MISO/(TIM1_BKIN)_31") (pintype "passive"))
    )
    (net (code "68") (name "/V_Thermal") (class "Default")
      (node (ref "P9") (pin "7") (pinfunction "7_7") (pintype "passive"))
      (node (ref "U1") (pin "32") (pinfunction "PA7/ADC12_IN7/TIM3_CH2/TIM8_CH1N/SPI1_MOSI(TIM1_CH1N)_32") (pintype "passive"))
    )
    (net (code "69") (name "/Z+") (class "Default")
      (node (ref "C17") (pin "1") (pinfunction "1_1") (pintype "passive"))
      (node (ref "P7") (pin "5") (pinfunction "5_5") (pintype "passive"))
      (node (ref "R9") (pin "2") (pinfunction "2_2") (pintype "passive"))
      (node (ref "U3") (pin "10") (pinfunction "InPut+_10") (pintype "passive"))
    )
    (net (code "70") (name "/Z-") (class "Default")
      (node (ref "C16") (pin "1") (pinfunction "1_1") (pintype "passive"))
      (node (ref "P7") (pin "6") (pinfunction "6_6") (pintype "passive"))
      (node (ref "R8") (pin "2") (pinfunction "2_2") (pintype "passive"))
      (node (ref "U3") (pin "9") (pinfunction "InPut-_9") (pintype "passive"))
    )
    (net (code "71") (name "3V3") (class "Default")
      (node (ref "C1") (pin "2") (pintype "passive"))
      (node (ref "C12") (pin "2") (pinfunction "2_2") (pintype "passive"))
      (node (ref "C2") (pin "2") (pintype "passive"))
      (node (ref "C22") (pin "2") (pinfunction "2_2") (pintype "passive"))
      (node (ref "C23") (pin "2") (pinfunction "2_2") (pintype "passive"))
      (node (ref "C3") (pin "2") (pintype "passive"))
      (node (ref "C4") (pin "2") (pintype "passive"))
      (node (ref "C6") (pin "2") (pinfunction "2_2") (pintype "passive"))
      (node (ref "L1") (pin "1") (pinfunction "1_1") (pintype "passive"))
      (node (ref "P10") (pin "1") (pinfunction "1_1") (pintype "passive"))
      (node (ref "P3") (pin "1") (pinfunction "1_1") (pintype "passive"))
      (node (ref "P9") (pin "17") (pinfunction "17_17") (pintype "passive"))
      (node (ref "R19") (pin "1") (pinfunction "1_1") (pintype "passive"))
      (node (ref "R3") (pin "2") (pintype "passive"))
      (node (ref "R4") (pin "2") (pintype "passive"))
      (node (ref "R5") (pin "1") (pintype "passive"))
      (node (ref "R6") (pin "1") (pintype "passive"))
      (node (ref "R7") (pin "1") (pintype "passive"))
      (node (ref "U1") (pin "100") (pinfunction "VDD_3_100") (pintype "passive"))
      (node (ref "U1") (pin "11") (pinfunction "VDD_5_11") (pintype "passive"))
      (node (ref "U1") (pin "19") (pinfunction "VDD_19") (pintype "passive"))
      (node (ref "U1") (pin "28") (pinfunction "VDD_4_28") (pintype "passive"))
      (node (ref "U1") (pin "50") (pinfunction "VDD_1_50") (pintype "passive"))
      (node (ref "U1") (pin "6") (pinfunction "VBAT_6") (pintype "passive"))
      (node (ref "U1") (pin "75") (pinfunction "VDD_2_75") (pintype "passive"))
      (node (ref "U2") (pin "2") (pinfunction "OUT_2") (pintype "passive"))
      (node (ref "U2") (pin "4") (pinfunction "OUT_4") (pintype "passive"))
      (node (ref "U4") (pin "3") (pinfunction "VCC_3") (pintype "passive"))
      (node (ref "U5") (pin "8") (pinfunction "VCC_8") (pintype "passive"))
    )
    (net (code "72") (name "3V3A") (class "Default")
      (node (ref "C13") (pin "2") (pinfunction "2_2") (pintype "passive"))
      (node (ref "L1") (pin "2") (pinfunction "2_2") (pintype "passive"))
      (node (ref "U1") (pin "21") (pinfunction "VREF+_21") (pintype "passive"))
      (node (ref "U1") (pin "22") (pinfunction "VDDA_22") (pintype "passive"))
    )
    (net (code "73") (name "5V") (class "Default")
      (node (ref "C14") (pin "1") (pinfunction "1_1") (pintype "passive"))
      (node (ref "C15") (pin "1") (pinfunction "1_1") (pintype "passive"))
      (node (ref "C24") (pin "1") (pintype "passive"))
      (node (ref "C26") (pin "1") (pintype "passive"))
      (node (ref "C27") (pin "2") (pintype "passive"))
      (node (ref "F1") (pin "1") (pintype "passive"))
      (node (ref "F2") (pin "1") (pintype "passive"))
      (node (ref "P4") (pin "2") (pinfunction "2_2") (pintype "passive"))
      (node (ref "P5") (pin "2") (pinfunction "2_2") (pintype "passive"))
      (node (ref "P7") (pin "7") (pinfunction "7_7") (pintype "passive"))
      (node (ref "P9") (pin "15") (pinfunction "15_15") (pintype "passive"))
      (node (ref "R10") (pin "1") (pinfunction "1_1") (pintype "passive"))
      (node (ref "R11") (pin "1") (pinfunction "1_1") (pintype "passive"))
      (node (ref "R12") (pin "1") (pinfunction "1_1") (pintype "passive"))
      (node (ref "R13") (pin "1") (pinfunction "1_1") (pintype "passive"))
      (node (ref "R8") (pin "1") (pinfunction "1_1") (pintype "passive"))
      (node (ref "R9") (pin "1") (pinfunction "1_1") (pintype "passive"))
      (node (ref "U3") (pin "12") (pinfunction "Control_12") (pintype "passive"))
      (node (ref "U3") (pin "16") (pinfunction "VCC_16") (pintype "passive"))
      (node (ref "U3") (pin "4") (pinfunction "Control_4") (pintype "passive"))
      (node (ref "U6") (pin "16") (pinfunction "VCC_16") (pintype "passive"))
    )
    (net (code "74") (name "AGND") (class "Default")
      (node (ref "C13") (pin "1") (pinfunction "1_1") (pintype "passive"))
      (node (ref "L2") (pin "2") (pinfunction "2_2") (pintype "passive"))
      (node (ref "U1") (pin "20") (pinfunction "VREF-_20") (pintype "passive"))
    )
    (net (code "75") (name "GND") (class "Default")
      (node (ref "B1") (pin "1") (pinfunction "1_1") (pintype "passive"))
      (node (ref "C1") (pin "1") (pintype "passive"))
      (node (ref "C10") (pin "1") (pintype "passive"))
      (node (ref "C11") (pin "1") (pintype "passive"))
      (node (ref "C12") (pin "1") (pinfunction "1_1") (pintype "passive"))
      (node (ref "C14") (pin "2") (pinfunction "2_2") (pintype "passive"))
      (node (ref "C15") (pin "2") (pinfunction "2_2") (pintype "passive"))
      (node (ref "C16") (pin "2") (pinfunction "2_2") (pintype "passive"))
      (node (ref "C17") (pin "2") (pinfunction "2_2") (pintype "passive"))
      (node (ref "C18") (pin "2") (pinfunction "2_2") (pintype "passive"))
      (node (ref "C19") (pin "2") (pinfunction "2_2") (pintype "passive"))
      (node (ref "C2") (pin "1") (pintype "passive"))
      (node (ref "C20") (pin "2") (pinfunction "2_2") (pintype "passive"))
      (node (ref "C21") (pin "2") (pinfunction "2_2") (pintype "passive"))
      (node (ref "C22") (pin "1") (pinfunction "1_1") (pintype "passive"))
      (node (ref "C23") (pin "1") (pinfunction "1_1") (pintype "passive"))
      (node (ref "C24") (pin "2") (pintype "passive"))
      (node (ref "C25") (pin "1") (pintype "passive"))
      (node (ref "C26") (pin "2") (pintype "passive"))
      (node (ref "C27") (pin "1") (pintype "passive"))
      (node (ref "C28") (pin "1") (pintype "passive"))
      (node (ref "C29") (pin "1") (pintype "passive"))
      (node (ref "C3") (pin "1") (pintype "passive"))
      (node (ref "C4") (pin "1") (pintype "passive"))
      (node (ref "C5") (pin "1") (pinfunction "1_1") (pintype "passive"))
      (node (ref "C6") (pin "1") (pinfunction "1_1") (pintype "passive"))
      (node (ref "C7") (pin "1") (pintype "passive"))
      (node (ref "C8") (pin "1") (pintype "passive"))
      (node (ref "C9") (pin "1") (pintype "passive"))
      (node (ref "D1") (pin "2") (pinfunction "K_2") (pintype "passive"))
      (node (ref "HOLE1") (pin "1") (pintype "passive"))
      (node (ref "HOLE2") (pin "1") (pintype "passive"))
      (node (ref "HOLE3") (pin "1") (pintype "passive"))
      (node (ref "HOLE4") (pin "1") (pintype "passive"))
      (node (ref "L2") (pin "1") (pinfunction "1_1") (pintype "passive"))
      (node (ref "P1") (pin "3") (pinfunction "3_3") (pintype "passive"))
      (node (ref "P1") (pin "4") (pinfunction "4_4") (pintype "passive"))
      (node (ref "P10") (pin "2") (pinfunction "2_2") (pintype "passive"))
      (node (ref "P11") (pin "1") (pinfunction "1_1") (pintype "passive"))
      (node (ref "P3") (pin "2") (pinfunction "2_2") (pintype "passive"))
      (node (ref "P4") (pin "1") (pinfunction "1_1") (pintype "passive"))
      (node (ref "P5") (pin "1") (pinfunction "1_1") (pintype "passive"))
      (node (ref "P7") (pin "8") (pinfunction "8_8") (pintype "passive"))
      (node (ref "P9") (pin "19") (pinfunction "19_19") (pintype "passive"))
      (node (ref "P9") (pin "20") (pinfunction "20_20") (pintype "passive"))
      (node (ref "R1") (pin "1") (pintype "passive"))
      (node (ref "R18") (pin "1") (pinfunction "1_1") (pintype "passive"))
      (node (ref "R2") (pin "2") (pintype "passive"))
      (node (ref "U1") (pin "10") (pinfunction "VSS_5_10") (pintype "passive"))
      (node (ref "U1") (pin "27") (pinfunction "VSS_4_27") (pintype "passive"))
      (node (ref "U1") (pin "74") (pinfunction "VSS_2_74") (pintype "passive"))
      (node (ref "U1") (pin "99") (pinfunction "VSS_3_99") (pintype "passive"))
      (node (ref "U2") (pin "1") (pinfunction "GND_1") (pintype "passive"))
      (node (ref "U3") (pin "14") (pinfunction "InPut+_14") (pintype "passive"))
      (node (ref "U3") (pin "15") (pinfunction "InPut-_15") (pintype "passive"))
      (node (ref "U3") (pin "8") (pinfunction "GND_8") (pintype "passive"))
      (node (ref "U4") (pin "2") (pinfunction "GND_2") (pintype "passive"))
      (node (ref "U4") (pin "8") (pinfunction "Rs_8") (pintype "passive"))
      (node (ref "U5") (pin "5") (pinfunction "GND_5") (pintype "passive"))
      (node (ref "U6") (pin "1") (pinfunction "GND_1") (pintype "passive"))
      (node (ref "USB_1") (pin "5") (pinfunction "GND_5") (pintype "passive"))
    )
    (net (code "76") (name "Net-(1-OSC1)") (class "Default")
      (node (ref "1") (pin "1") (pinfunction "OSC1_1") (pintype "passive"))
      (node (ref "C29") (pin "2") (pintype "passive"))
      (node (ref "U6") (pin "8") (pinfunction "XO_8") (pintype "passive"))
    )
    (net (code "77") (name "Net-(D1-A)") (class "Default")
      (node (ref "D1") (pin "1") (pinfunction "A_1") (pintype "passive"))
      (node (ref "R3") (pin "1") (pintype "passive"))
    )
    (net (code "78") (name "Net-(D2-A)") (class "Default")
      (node (ref "D2") (pin "1") (pinfunction "A_1") (pintype "passive"))
      (node (ref "R5") (pin "2") (pintype "passive"))
    )
    (net (code "79") (name "Net-(D3-A)") (class "Default")
      (node (ref "D3") (pin "1") (pinfunction "A_1") (pintype "passive"))
      (node (ref "R6") (pin "2") (pintype "passive"))
    )
    (net (code "80") (name "Net-(D4-A)") (class "Default")
      (node (ref "D4") (pin "1") (pinfunction "A_1") (pintype "passive"))
      (node (ref "R7") (pin "2") (pintype "passive"))
    )
    (net (code "81") (name "Net-(U1-BOOT0)") (class "Default")
      (node (ref "R2") (pin "1") (pintype "passive"))
      (node (ref "U1") (pin "94") (pinfunction "BOOT0_94") (pintype "passive"))
    )
    (net (code "82") (name "Net-(U1-BOOT1{slash}PB2)") (class "Default")
      (node (ref "R1") (pin "2") (pintype "passive"))
      (node (ref "U1") (pin "37") (pinfunction "BOOT1/PB2_37") (pintype "passive"))
    )
    (net (code "83") (name "Net-(U1-OSC_IN)") (class "Default")
      (node (ref "C10") (pin "2") (pintype "passive"))
      (node (ref "U1") (pin "12") (pinfunction "OSC_IN_12") (pintype "passive"))
      (node (ref "Y1") (pin "3") (pinfunction "OSC2_3") (pintype "passive"))
    )
    (net (code "84") (name "Net-(U1-OSC_OUT)") (class "Default")
      (node (ref "C11") (pin "2") (pintype "passive"))
      (node (ref "U1") (pin "13") (pinfunction "OSC_OUT_13") (pintype "passive"))
      (node (ref "Y1") (pin "1") (pinfunction "OSC1_1") (pintype "passive"))
    )
    (net (code "85") (name "Net-(U1-VCAP_1)") (class "Default")
      (node (ref "C7") (pin "2") (pintype "passive"))
      (node (ref "U1") (pin "49") (pinfunction "VCAP_1_49") (pintype "passive"))
    )
    (net (code "86") (name "Net-(U1-VCAP_2)") (class "Default")
      (node (ref "C9") (pin "2") (pintype "passive"))
      (node (ref "U1") (pin "73") (pinfunction "VCAP_2_73") (pintype "passive"))
    )
    (net (code "87") (name "Net-(U2-IN)") (class "Default")
      (node (ref "C5") (pin "2") (pinfunction "2_2") (pintype "passive"))
      (node (ref "F1") (pin "2") (pintype "passive"))
      (node (ref "U2") (pin "3") (pinfunction "IN_3") (pintype "passive"))
    )
    (net (code "88") (name "Net-(U3-OutPutA)") (class "Default")
      (node (ref "R14") (pin "1") (pinfunction "1_1") (pintype "passive"))
      (node (ref "U3") (pin "3") (pinfunction "OutPutA_3") (pintype "passive"))
    )
    (net (code "89") (name "Net-(U3-OutPutB)") (class "Default")
      (node (ref "R15") (pin "1") (pinfunction "1_1") (pintype "passive"))
      (node (ref "U3") (pin "5") (pinfunction "OutPutB_5") (pintype "passive"))
    )
    (net (code "90") (name "Net-(U3-OutPutC)") (class "Default")
      (node (ref "R16") (pin "1") (pinfunction "1_1") (pintype "passive"))
      (node (ref "U3") (pin "11") (pinfunction "OutPutC_11") (pintype "passive"))
    )
    (net (code "91") (name "Net-(U4-CANH)") (class "Default")
      (node (ref "P6") (pin "1") (pinfunction "1_1") (pintype "passive"))
      (node (ref "R17") (pin "1") (pinfunction "1_1") (pintype "passive"))
      (node (ref "U4") (pin "7") (pinfunction "CANH_7") (pintype "passive"))
    )
    (net (code "92") (name "Net-(U4-CANL)") (class "Default")
      (node (ref "P6") (pin "2") (pinfunction "2_2") (pintype "passive"))
      (node (ref "R17") (pin "2") (pinfunction "2_2") (pintype "passive"))
      (node (ref "U4") (pin "6") (pinfunction "CANL_6") (pintype "passive"))
    )
    (net (code "93") (name "Net-(U5-A)") (class "Default")
      (node (ref "P8") (pin "2") (pinfunction "2_2") (pintype "passive"))
      (node (ref "R19") (pin "2") (pinfunction "2_2") (pintype "passive"))
      (node (ref "R20") (pin "2") (pinfunction "2_2") (pintype "passive"))
      (node (ref "U5") (pin "6") (pinfunction "A_6") (pintype "passive"))
    )
    (net (code "94") (name "Net-(U5-B)") (class "Default")
      (node (ref "P8") (pin "1") (pinfunction "1_1") (pintype "passive"))
      (node (ref "R18") (pin "2") (pinfunction "2_2") (pintype "passive"))
      (node (ref "R20") (pin "1") (pinfunction "1_1") (pintype "passive"))
      (node (ref "U5") (pin "7") (pinfunction "B_7") (pintype "passive"))
    )
    (net (code "95") (name "Net-(U6-V3)") (class "Default")
      (node (ref "C25") (pin "2") (pintype "passive"))
      (node (ref "U6") (pin "4") (pinfunction "V3_4") (pintype "passive"))
    )
    (net (code "96") (name "Net-(U6-XI)") (class "Default")
      (node (ref "1") (pin "3") (pinfunction "OSC2_3") (pintype "passive"))
      (node (ref "C28") (pin "2") (pintype "passive"))
      (node (ref "U6") (pin "7") (pinfunction "XI_7") (pintype "passive"))
    )
    (net (code "97") (name "Net-(USB_1-VCC)") (class "Default")
      (node (ref "F2") (pin "2") (pintype "passive"))
      (node (ref "USB_1") (pin "1") (pinfunction "VCC_1") (pintype "passive"))
    )
    (net (code "98") (name "unconnected-(1-OSC2-Pad2)") (class "Default")
      (node (ref "1") (pin "2") (pinfunction "OSC2_2") (pintype "passive"))
    )
    (net (code "99") (name "unconnected-(1-OSC2-Pad4)") (class "Default")
      (node (ref "1") (pin "4") (pinfunction "OSC2_4") (pintype "passive"))
    )
    (net (code "100") (name "unconnected-(P9-Pad13)") (class "Default")
      (node (ref "P9") (pin "13") (pinfunction "13_13") (pintype "passive"))
    )
    (net (code "101") (name "unconnected-(U1-(TIM1_CH2N){slash}TIM8_CH2N{slash}TIM3_CH3{slash}AD12_IN8{slash}PB0-Pad35)") (class "Default")
      (node (ref "U1") (pin "35") (pinfunction "(TIM1_CH2N)/TIM8_CH2N/TIM3_CH3/AD12_IN8/PB0_35") (pintype "passive"))
    )
    (net (code "102") (name "unconnected-(U1-(TIM1_CH3N){slash}TIM8_CH3{slash}TIM3_CH4{slash}ADC12_IN9{slash}PB1-Pad36)") (class "Default")
      (node (ref "U1") (pin "36") (pinfunction "(TIM1_CH3N)/TIM8_CH3/TIM3_CH4/ADC12_IN9/PB1_36") (pintype "passive"))
    )
    (net (code "103") (name "unconnected-(U1-FSMC_NBL1{slash}PE1-Pad98)") (class "Default")
      (node (ref "U1") (pin "98") (pinfunction "FSMC_NBL1/PE1_98") (pintype "passive"))
    )
    (net (code "104") (name "unconnected-(U1-PA3{slash}ADC123_IN3{slash}USART2_RX{slash}TIM2_CH4{slash}TIM5_CH4-Pad26)") (class "Default")
      (node (ref "U1") (pin "26") (pinfunction "PA3/ADC123_IN3/USART2_RX/TIM2_CH4/TIM5_CH4_26") (pintype "passive"))
    )
    (net (code "105") (name "unconnected-(U1-PA15{slash}JTDI{slash}I2S3_WS{slash}SPI3_NSS{slash}(TIM2_CH1_ETR{slash}SPI1_NSS)-Pad77)") (class "Default")
      (node (ref "U1") (pin "77") (pinfunction "PA15/JTDI/I2S3_WS/SPI3_NSS/(TIM2_CH1_ETR/SPI1_NSS)_77") (pintype "passive"))
    )
    (net (code "106") (name "unconnected-(U1-PC3{slash}ADC123_IN13-Pad18)") (class "Default")
      (node (ref "U1") (pin "18") (pinfunction "PC3/ADC123_IN13_18") (pintype "passive"))
    )
    (net (code "107") (name "unconnected-(U1-PC4{slash}ADC12_IN14-Pad33)") (class "Default")
      (node (ref "U1") (pin "33") (pinfunction "PC4/ADC12_IN14_33") (pintype "passive"))
    )
    (net (code "108") (name "unconnected-(U1-PC5{slash}ADC12_IN15-Pad34)") (class "Default")
      (node (ref "U1") (pin "34") (pinfunction "PC5/ADC12_IN15_34") (pintype "passive"))
    )
    (net (code "109") (name "unconnected-(U1-PC9{slash}TIM8_CH4{slash}SIDO_D1(TIM3_CH4)-Pad66)") (class "Default")
      (node (ref "U1") (pin "66") (pinfunction "PC9/TIM8_CH4/SIDO_D1(TIM3_CH4)_66") (pintype "passive"))
    )
    (net (code "110") (name "unconnected-(U1-PC13{slash}TAMPER-RTC-Pad7)") (class "Default")
      (node (ref "U1") (pin "7") (pinfunction "PC13/TAMPER-RTC_7") (pintype "passive"))
    )
    (net (code "111") (name "unconnected-(U1-PC14{slash}OSC32_IN-Pad8)") (class "Default")
      (node (ref "U1") (pin "8") (pinfunction "PC14/OSC32_IN_8") (pintype "passive"))
    )
    (net (code "112") (name "unconnected-(U1-PC15{slash}OSC32_OUT-Pad9)") (class "Default")
      (node (ref "U1") (pin "9") (pinfunction "PC15/OSC32_OUT_9") (pintype "passive"))
    )
    (net (code "113") (name "unconnected-(U1-PD6{slash}FSMC_NWAIT{slash}(USART2_RX)-Pad87)") (class "Default")
      (node (ref "U1") (pin "87") (pinfunction "PD6/FSMC_NWAIT/(USART2_RX)_87") (pintype "passive"))
    )
    (net (code "114") (name "unconnected-(U1-PD11{slash}FSMC_A16{slash}(USART3_CTS)-Pad58)") (class "Default")
      (node (ref "U1") (pin "58") (pinfunction "PD11/FSMC_A16/(USART3_CTS)_58") (pintype "passive"))
    )
    (net (code "115") (name "unconnected-(U1-PD12{slash}FSMC_A17{slash}(USART3_RTS{slash}TIM4_CH1)-Pad59)") (class "Default")
      (node (ref "U1") (pin "59") (pinfunction "PD12/FSMC_A17/(USART3_RTS/TIM4_CH1)_59") (pintype "passive"))
    )
    (net (code "116") (name "unconnected-(U1-TIM4_ETR{slash}FSMC_NBL0{slash}PE0-Pad97)") (class "Default")
      (node (ref "U1") (pin "97") (pinfunction "TIM4_ETR/FSMC_NBL0/PE0_97") (pintype "passive"))
    )
    (net (code "117") (name "unconnected-(U1-TRACED2{slash}FSMC_A21{slash}PE5-Pad4)") (class "Default")
      (node (ref "U1") (pin "4") (pinfunction "TRACED2/FSMC_A21/PE5_4") (pintype "passive"))
    )
    (net (code "118") (name "unconnected-(U1-TRACED3{slash}FSMC_A22{slash}PE6-Pad5)") (class "Default")
      (node (ref "U1") (pin "5") (pinfunction "TRACED3/FSMC_A22/PE6_5") (pintype "passive"))
    )
    (net (code "119") (name "unconnected-(U3-OutPutD-Pad13)") (class "Default")
      (node (ref "U3") (pin "13") (pinfunction "OutPutD_13") (pintype "passive"))
    )
    (net (code "120") (name "unconnected-(U4-Vref-Pad5)") (class "Default")
      (node (ref "U4") (pin "5") (pinfunction "Vref_5") (pintype "passive"))
    )
    (net (code "121") (name "unconnected-(U6-CTS#-Pad9)") (class "Default")
      (node (ref "U6") (pin "9") (pinfunction "CTS#_9") (pintype "passive"))
    )
    (net (code "122") (name "unconnected-(U6-DCD#-Pad12)") (class "Default")
      (node (ref "U6") (pin "12") (pinfunction "DCD#_12") (pintype "passive"))
    )
    (net (code "123") (name "unconnected-(U6-DSR#-Pad10)") (class "Default")
      (node (ref "U6") (pin "10") (pinfunction "DSR#_10") (pintype "passive"))
    )
    (net (code "124") (name "unconnected-(U6-DTR#-Pad13)") (class "Default")
      (node (ref "U6") (pin "13") (pinfunction "DTR#_13") (pintype "passive"))
    )
    (net (code "125") (name "unconnected-(U6-R232-Pad15)") (class "Default")
      (node (ref "U6") (pin "15") (pinfunction "R232_15") (pintype "passive"))
    )
    (net (code "126") (name "unconnected-(U6-RI#-Pad11)") (class "Default")
      (node (ref "U6") (pin "11") (pinfunction "RI#_11") (pintype "passive"))
    )
    (net (code "127") (name "unconnected-(U6-RTS#-Pad14)") (class "Default")
      (node (ref "U6") (pin "14") (pinfunction "RTS#_14") (pintype "passive"))
    )
    (net (code "128") (name "unconnected-(USB_1-NC-Pad4)") (class "Default")
      (node (ref "USB_1") (pin "4") (pinfunction "NC_4") (pintype "passive"))
    )
    (net (code "129") (name "unconnected-(Y1-OSC2-Pad2)") (class "Default")
      (node (ref "Y1") (pin "2") (pinfunction "OSC2_2") (pintype "passive"))
    )
    (net (code "130") (name "unconnected-(Y1-OSC2-Pad4)") (class "Default")
      (node (ref "Y1") (pin "4") (pinfunction "OSC2_4") (pintype "passive"))
    )
  )
)
